# receiver_by_chandan.net
KiCad netlist of a schematic drawn in EasyEDA Pro
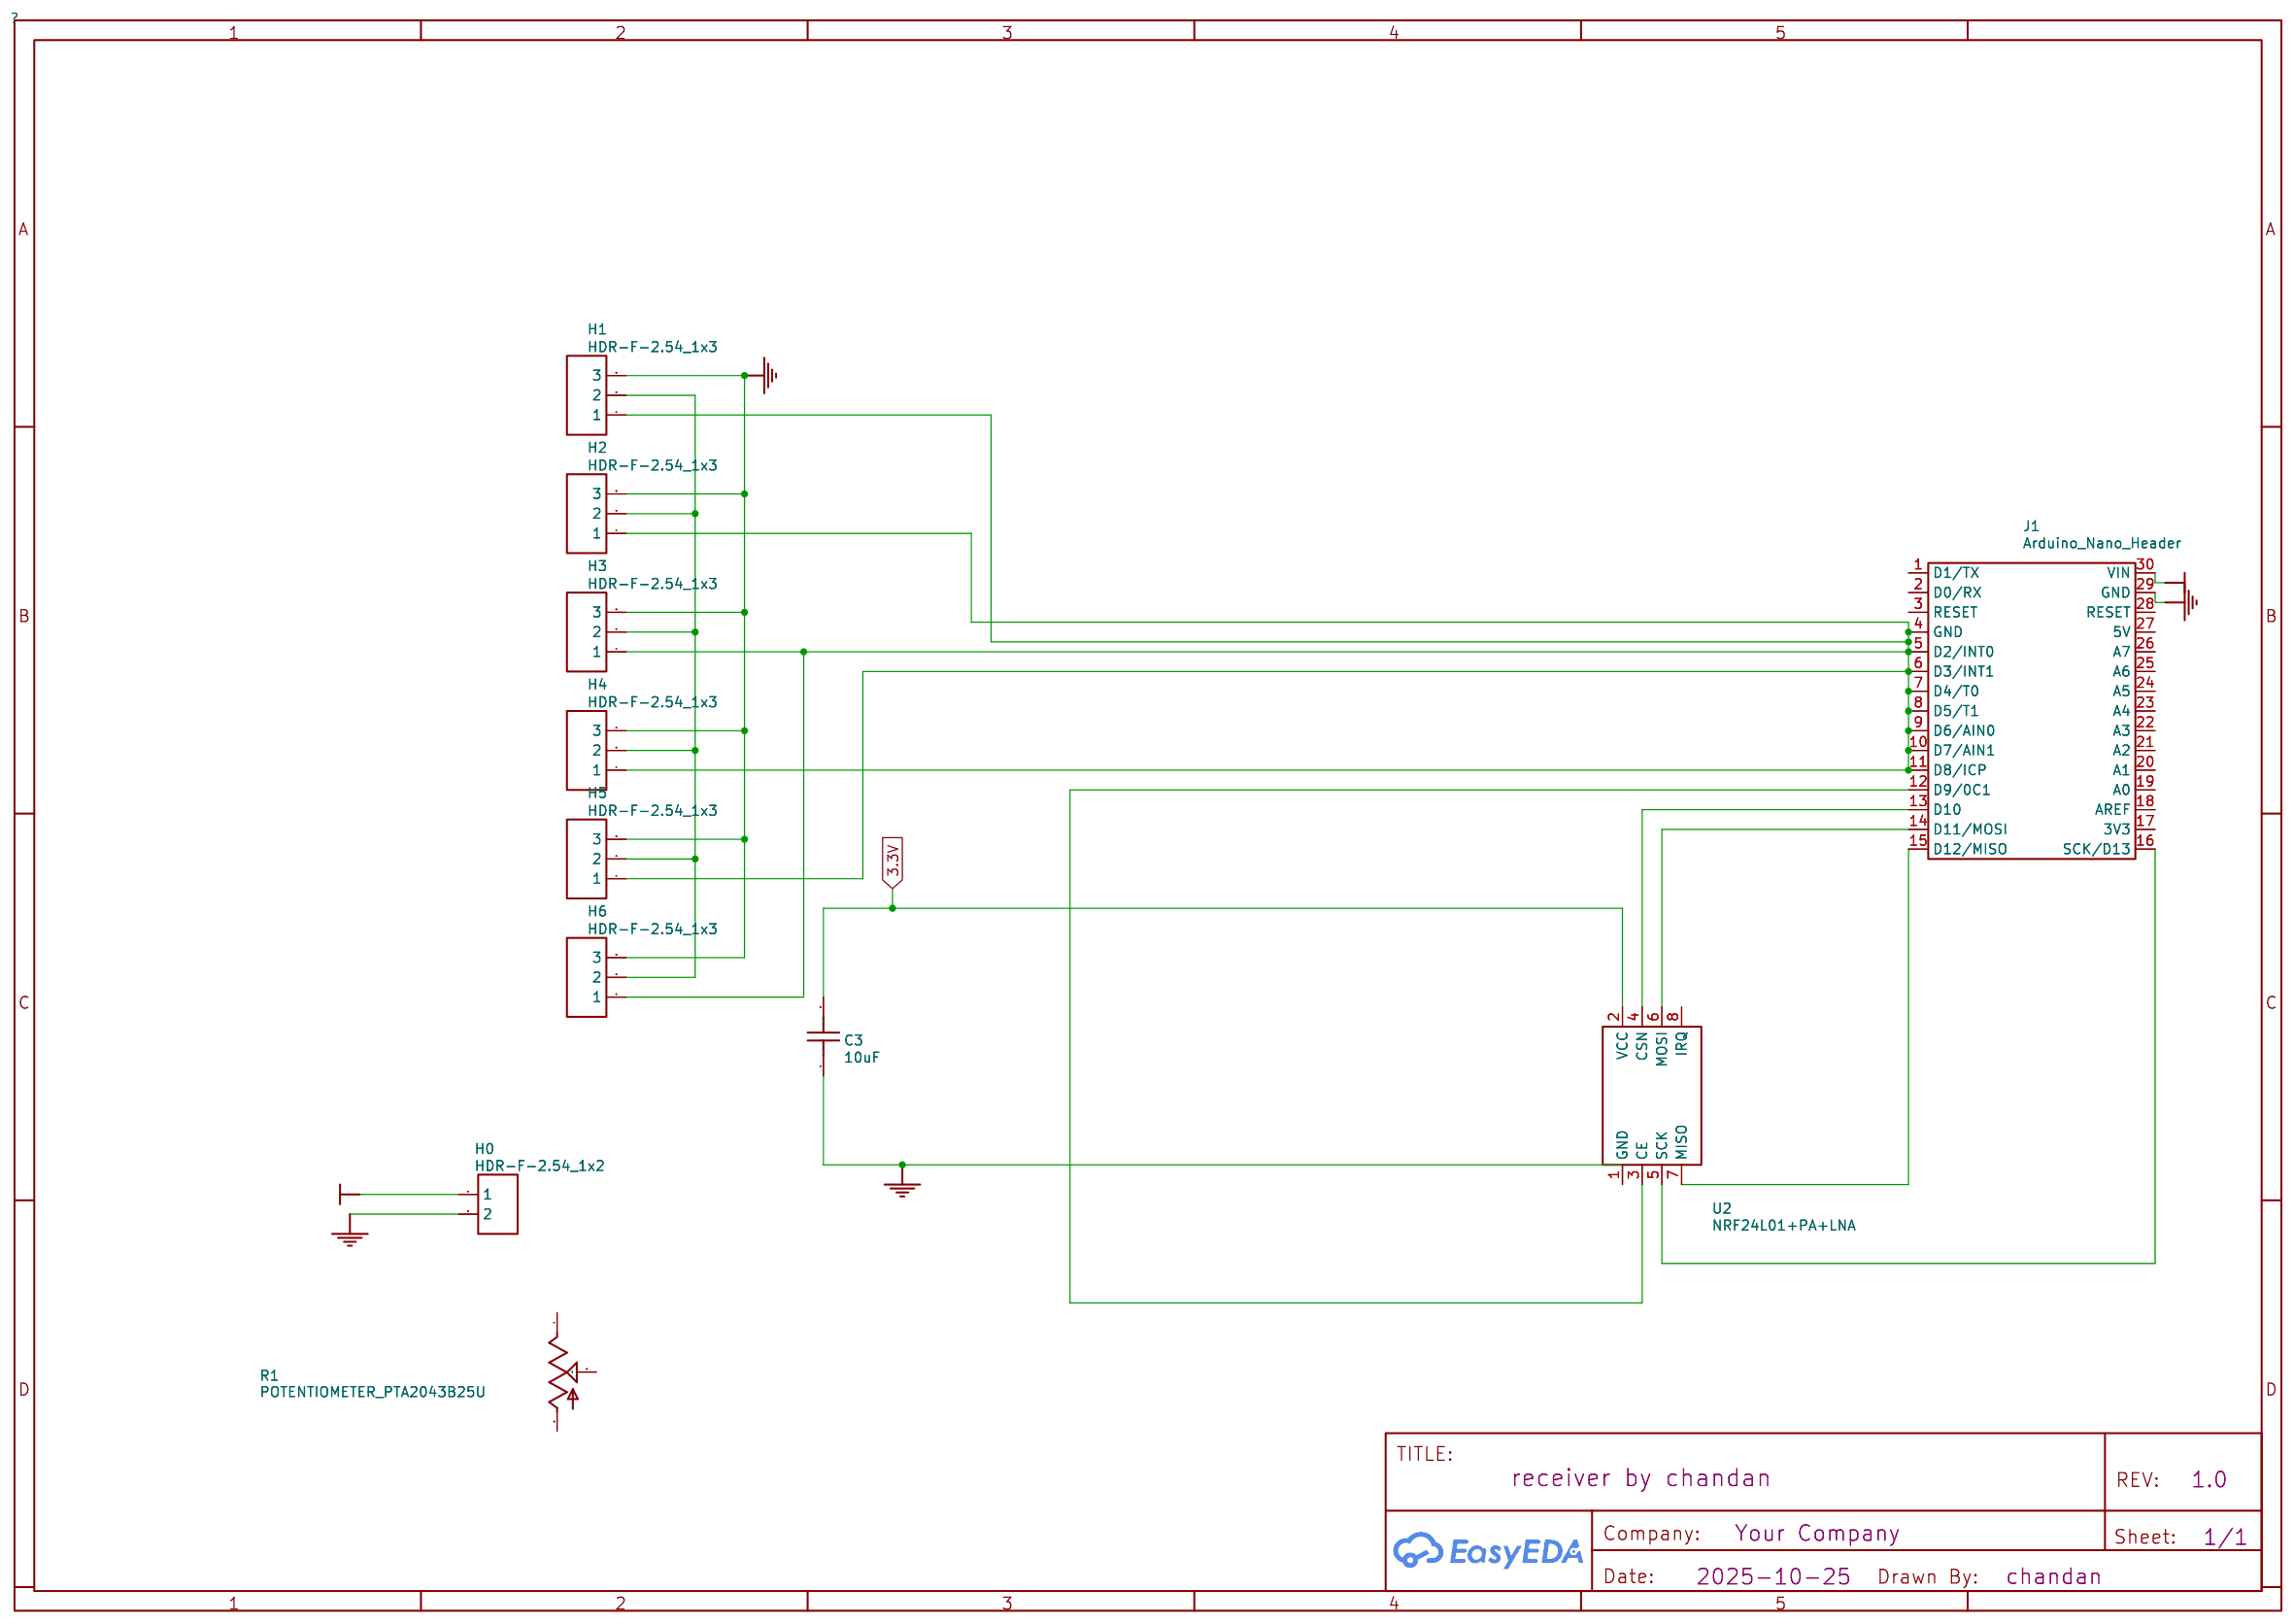
[diagram p0: schematic sheet]

(export (version "E")
  (design (tool "Eeschema 10.0.6"))
  (components
    (comp (ref "C3")
      (value "10uF")
      (fields
        (field (name "Manufacturer Part") "FK16X5R1H105K")
        (field (name "Manufacturer") "TDK")
        (field (name "Contributor") "lcsc")
      )
      (libsource (lib "easyedapro") (part "10uF"))
    )
    (comp (ref "H0")
      (value "HDR-F-2.54_1x2")
      (fields (field (name "Contributor") "LCEDA_Lib"))
      (libsource (lib "easyedapro") (part "HDR-F-2.54_1x2"))
    )
    (comp (ref "H1")
      (value "HDR-F-2.54_1x3")
      (fields (field (name "Contributor") "LCEDA_Lib"))
      (libsource (lib "easyedapro") (part "HDR-F-2.54_1x3"))
    )
    (comp (ref "H2")
      (value "HDR-F-2.54_1x3")
      (fields (field (name "Contributor") "LCEDA_Lib"))
      (libsource (lib "easyedapro") (part "HDR-F-2.54_1x3"))
    )
    (comp (ref "H3")
      (value "HDR-F-2.54_1x3")
      (fields (field (name "Contributor") "LCEDA_Lib"))
      (libsource (lib "easyedapro") (part "HDR-F-2.54_1x3"))
    )
    (comp (ref "H4")
      (value "HDR-F-2.54_1x3")
      (fields (field (name "Contributor") "LCEDA_Lib"))
      (libsource (lib "easyedapro") (part "HDR-F-2.54_1x3"))
    )
    (comp (ref "H5")
      (value "HDR-F-2.54_1x3")
      (fields (field (name "Contributor") "LCEDA_Lib"))
      (libsource (lib "easyedapro") (part "HDR-F-2.54_1x3"))
    )
    (comp (ref "H6")
      (value "HDR-F-2.54_1x3")
      (fields (field (name "Contributor") "LCEDA_Lib"))
      (libsource (lib "easyedapro") (part "HDR-F-2.54_1x3"))
    )
    (comp (ref "J1")
      (value "Arduino_Nano_Header")
      (libsource (lib "easyedapro") (part "Arduino_Nano_Header"))
    )
    (comp (ref "R1")
      (value "POTENTIOMETER_PTA2043B25U")
      (fields (field (name "Contributor") "mymindstorm"))
      (libsource (lib "easyedapro") (part "POTENTIOMETER_PTA2043B25U"))
    )
    (comp (ref "U2")
      (value "NRF24L01+PA+LNA")
      (fields (field (name "Manufacturer Part") "nRF24L01+PA+LNA") (field (name "Contributor") "lcsc"))
      (libsource (lib "easyedapro") (part "NRF24L01+PA+LNA"))
    )
  )
  (nets
    (net (code "1") (name "+5V") (class "Default")
      (node (ref "H0") (pin "1") (pinfunction "1_1") (pintype "input"))
      (node (ref "J1") (pin "30") (pinfunction "VIN_30") (pintype "unspecified"))
    )
    (net (code "2") (name "3.3V") (class "Default")
      (node (ref "C3") (pin "2") (pinfunction "2_2") (pintype "unspecified"))
      (node (ref "U2") (pin "2") (pinfunction "VCC_2") (pintype "unspecified"))
    )
    (net (code "3") (name "GND") (class "Default")
      (node (ref "C3") (pin "1") (pinfunction "1_1") (pintype "unspecified"))
      (node (ref "H0") (pin "2") (pinfunction "2_2") (pintype "input"))
      (node (ref "H1") (pin "3") (pinfunction "3_3") (pintype "input"))
      (node (ref "H2") (pin "3") (pinfunction "3_3") (pintype "input"))
      (node (ref "H3") (pin "3") (pinfunction "3_3") (pintype "input"))
      (node (ref "H4") (pin "3") (pinfunction "3_3") (pintype "input"))
      (node (ref "H5") (pin "3") (pinfunction "3_3") (pintype "input"))
      (node (ref "H6") (pin "3") (pinfunction "3_3") (pintype "input"))
      (node (ref "J1") (pin "29") (pinfunction "GND_29") (pintype "unspecified"))
      (node (ref "U2") (pin "1") (pinfunction "GND_1") (pintype "unspecified"))
    )
    (net (code "4") (name "Net-(H1-Pad2)") (class "Default")
      (node (ref "H1") (pin "2") (pinfunction "2_2") (pintype "input"))
      (node (ref "H2") (pin "2") (pinfunction "2_2") (pintype "input"))
      (node (ref "H3") (pin "2") (pinfunction "2_2") (pintype "input"))
      (node (ref "H4") (pin "2") (pinfunction "2_2") (pintype "input"))
      (node (ref "H5") (pin "2") (pinfunction "2_2") (pintype "input"))
      (node (ref "H6") (pin "2") (pinfunction "2_2") (pintype "input"))
    )
    (net (code "5") (name "Net-(J1-D2{slash}INT0)") (class "Default")
      (node (ref "H1") (pin "1") (pinfunction "1_1") (pintype "input"))
      (node (ref "H2") (pin "1") (pinfunction "1_1") (pintype "input"))
      (node (ref "H3") (pin "1") (pinfunction "1_1") (pintype "input"))
      (node (ref "H4") (pin "1") (pinfunction "1_1") (pintype "input"))
      (node (ref "H5") (pin "1") (pinfunction "1_1") (pintype "input"))
      (node (ref "H6") (pin "1") (pinfunction "1_1") (pintype "input"))
      (node (ref "J1") (pin "10") (pinfunction "D7/AIN1_10") (pintype "unspecified"))
      (node (ref "J1") (pin "11") (pinfunction "D8/ICP_11") (pintype "unspecified"))
      (node (ref "J1") (pin "4") (pinfunction "GND_4") (pintype "unspecified"))
      (node (ref "J1") (pin "5") (pinfunction "D2/INT0_5") (pintype "unspecified"))
      (node (ref "J1") (pin "6") (pinfunction "D3/INT1_6") (pintype "unspecified"))
      (node (ref "J1") (pin "7") (pinfunction "D4/T0_7") (pintype "unspecified"))
      (node (ref "J1") (pin "8") (pinfunction "D5/T1_8") (pintype "unspecified"))
      (node (ref "J1") (pin "9") (pinfunction "D6/AIN0_9") (pintype "unspecified"))
    )
    (net (code "6") (name "Net-(J1-D9{slash}0C1)") (class "Default")
      (node (ref "J1") (pin "12") (pinfunction "D9/0C1_12") (pintype "unspecified"))
      (node (ref "U2") (pin "3") (pinfunction "CE_3") (pintype "unspecified"))
    )
    (net (code "7") (name "Net-(J1-D10)") (class "Default")
      (node (ref "J1") (pin "13") (pinfunction "D10_13") (pintype "unspecified"))
      (node (ref "U2") (pin "4") (pinfunction "CSN_4") (pintype "unspecified"))
    )
    (net (code "8") (name "Net-(J1-D11{slash}MOSI)") (class "Default")
      (node (ref "J1") (pin "14") (pinfunction "D11/MOSI_14") (pintype "unspecified"))
      (node (ref "U2") (pin "6") (pinfunction "MOSI_6") (pintype "unspecified"))
    )
    (net (code "9") (name "Net-(J1-D12{slash}MISO)") (class "Default")
      (node (ref "J1") (pin "15") (pinfunction "D12/MISO_15") (pintype "unspecified"))
      (node (ref "U2") (pin "7") (pinfunction "MISO_7") (pintype "unspecified"))
    )
    (net (code "10") (name "Net-(J1-SCK{slash}D13)") (class "Default")
      (node (ref "J1") (pin "16") (pinfunction "SCK/D13_16") (pintype "unspecified"))
      (node (ref "U2") (pin "5") (pinfunction "SCK_5") (pintype "unspecified"))
    )
    (net (code "11") (name "unconnected-(J1-3V3-Pad17)") (class "Default")
      (node (ref "J1") (pin "17") (pinfunction "3V3_17") (pintype "unspecified"))
    )
    (net (code "12") (name "unconnected-(J1-5V-Pad27)") (class "Default")
      (node (ref "J1") (pin "27") (pinfunction "5V_27") (pintype "unspecified"))
    )
    (net (code "13") (name "unconnected-(J1-A0-Pad19)") (class "Default")
      (node (ref "J1") (pin "19") (pinfunction "A0_19") (pintype "unspecified"))
    )
    (net (code "14") (name "unconnected-(J1-A1-Pad20)") (class "Default")
      (node (ref "J1") (pin "20") (pinfunction "A1_20") (pintype "unspecified"))
    )
    (net (code "15") (name "unconnected-(J1-A2-Pad21)") (class "Default")
      (node (ref "J1") (pin "21") (pinfunction "A2_21") (pintype "unspecified"))
    )
    (net (code "16") (name "unconnected-(J1-A3-Pad22)") (class "Default")
      (node (ref "J1") (pin "22") (pinfunction "A3_22") (pintype "unspecified"))
    )
    (net (code "17") (name "unconnected-(J1-A4-Pad23)") (class "Default")
      (node (ref "J1") (pin "23") (pinfunction "A4_23") (pintype "unspecified"))
    )
    (net (code "18") (name "unconnected-(J1-A5-Pad24)") (class "Default")
      (node (ref "J1") (pin "24") (pinfunction "A5_24") (pintype "unspecified"))
    )
    (net (code "19") (name "unconnected-(J1-A6-Pad25)") (class "Default")
      (node (ref "J1") (pin "25") (pinfunction "A6_25") (pintype "unspecified"))
    )
    (net (code "20") (name "unconnected-(J1-A7-Pad26)") (class "Default")
      (node (ref "J1") (pin "26") (pinfunction "A7_26") (pintype "unspecified"))
    )
    (net (code "21") (name "unconnected-(J1-AREF-Pad18)") (class "Default")
      (node (ref "J1") (pin "18") (pinfunction "AREF_18") (pintype "unspecified"))
    )
    (net (code "22") (name "unconnected-(J1-D0{slash}RX-Pad2)") (class "Default")
      (node (ref "J1") (pin "2") (pinfunction "D0/RX_2") (pintype "unspecified"))
    )
    (net (code "23") (name "unconnected-(J1-D1{slash}TX-Pad1)") (class "Default")
      (node (ref "J1") (pin "1") (pinfunction "D1/TX_1") (pintype "unspecified"))
    )
    (net (code "24") (name "unconnected-(J1-RESET-Pad3)") (class "Default")
      (node (ref "J1") (pin "3") (pinfunction "RESET_3") (pintype "unspecified"))
    )
    (net (code "25") (name "unconnected-(J1-RESET-Pad28)") (class "Default")
      (node (ref "J1") (pin "28") (pinfunction "RESET_28") (pintype "unspecified"))
    )
    (net (code "26") (name "unconnected-(R1-A-Pad3)") (class "Default")
      (node (ref "R1") (pin "3") (pinfunction "A_3") (pintype "bidirectional"))
    )
    (net (code "27") (name "unconnected-(R1-E-Pad1)") (class "Default")
      (node (ref "R1") (pin "1") (pinfunction "E_1") (pintype "bidirectional"))
    )
    (net (code "28") (name "unconnected-(R1-S-Pad2)") (class "Default")
      (node (ref "R1") (pin "2") (pinfunction "S_2") (pintype "bidirectional"))
    )
    (net (code "29") (name "unconnected-(U2-IRQ-Pad8)") (class "Default")
      (node (ref "U2") (pin "8") (pinfunction "IRQ_8") (pintype "unspecified"))
    )
  )
)
